# sensor_board_v0_55.net
KiCad netlist of a schematic drawn in EAGLE
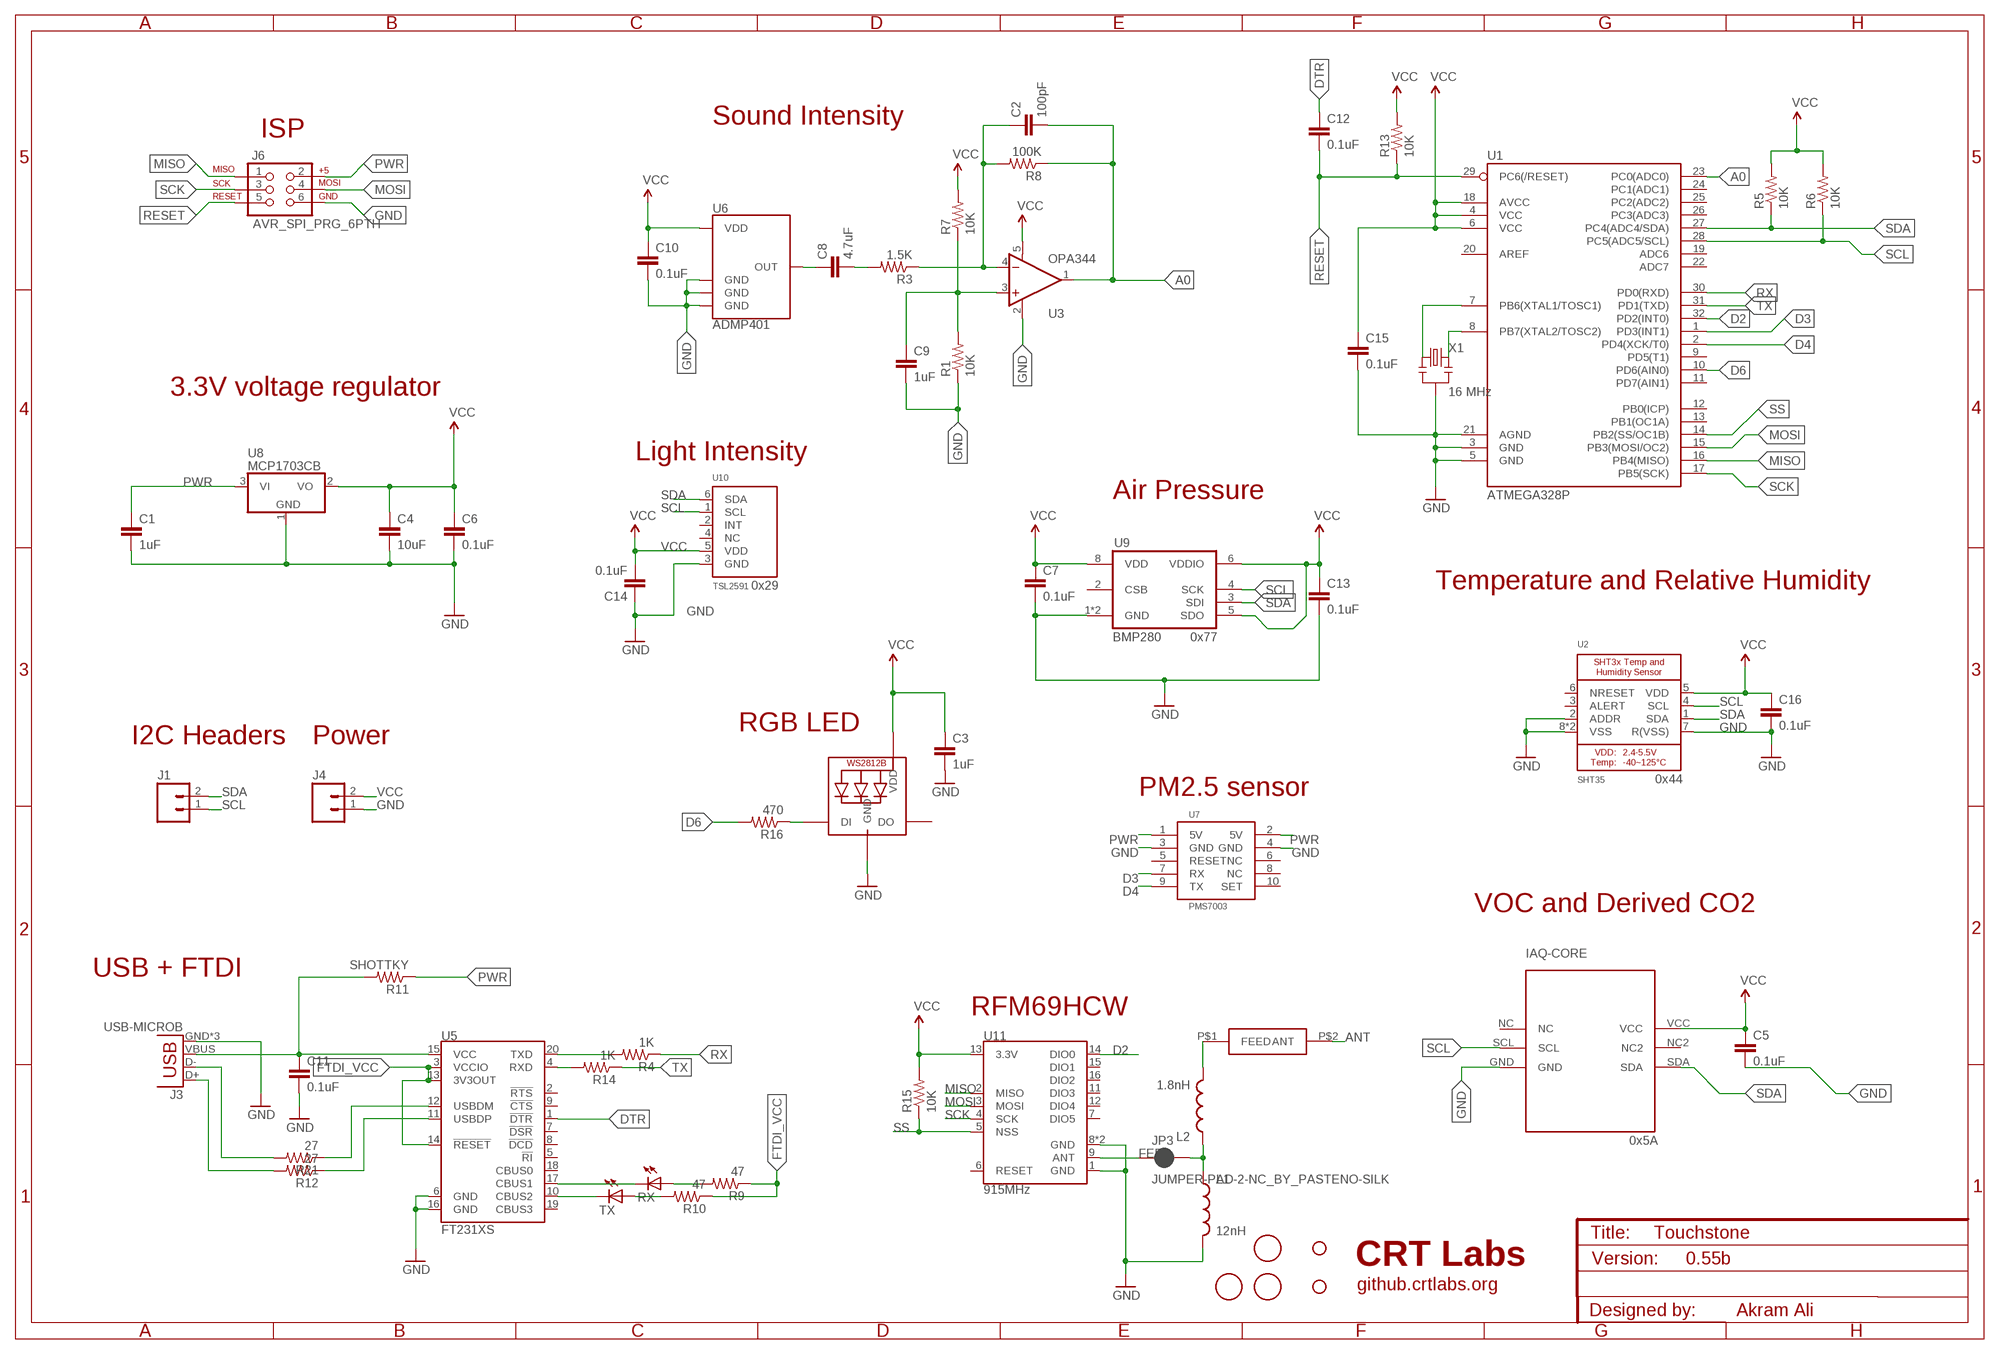
[diagram p0: schematic, sheet 1]

(export (version "E")
  (design (tool "Eeschema 10.0.6"))
  (components
    (comp (ref "C1")
      (value "1uF")
      (footprint "eagle-import:0805")
      (fields (field (name "MPN") "CC0805ZRY5V8BB105"))
      (libsource (lib "eagle-import") (part "CAP0805"))
    )
    (comp (ref "C2")
      (value "100pF")
      (footprint "eagle-import:0805")
      (fields (field (name "MPN") "CC0805JRNPOABN101"))
      (libsource (lib "eagle-import") (part "CAP0805"))
    )
    (comp (ref "C3")
      (value "1uF")
      (footprint "eagle-import:0805")
      (fields (field (name "MPN") "CC0805ZRY5V8BB105"))
      (libsource (lib "eagle-import") (part "CAP0805"))
    )
    (comp (ref "C4")
      (value "10uF")
      (footprint "eagle-import:0805")
      (fields (field (name "MPN") "CC0805KKX5R6BB106"))
      (libsource (lib "eagle-import") (part "CAP0805"))
    )
    (comp (ref "C5")
      (value "0.1uF")
      (footprint "eagle-import:0805")
      (fields (field (name "MPN") "CC0805KRX7R9BB104"))
      (libsource (lib "eagle-import") (part "SparkFun-Passives_CAP0805"))
    )
    (comp (ref "C6")
      (value "0.1uF")
      (footprint "eagle-import:0805")
      (fields (field (name "MPN") "CC0805KRX7R9BB104"))
      (libsource (lib "eagle-import") (part "CAP0805"))
    )
    (comp (ref "C7")
      (value "0.1uF")
      (footprint "eagle-import:0805")
      (fields (field (name "MPN") "CC0805KRX7R9BB104"))
      (libsource (lib "eagle-import") (part "SparkFun-Passives_CAP0805"))
    )
    (comp (ref "C8")
      (value "4.7uF")
      (footprint "eagle-import:0805")
      (fields (field (name "MPN") "CC0805KKX7R6BB475"))
      (libsource (lib "eagle-import") (part "CAP0805"))
    )
    (comp (ref "C9")
      (value "1uF")
      (footprint "eagle-import:0805")
      (fields (field (name "MPN") "CC0805ZRY5V8BB105"))
      (libsource (lib "eagle-import") (part "CAP0805"))
    )
    (comp (ref "C10")
      (value "0.1uF")
      (footprint "eagle-import:0805")
      (fields (field (name "MPN") "CC0805KRX7R9BB104"))
      (libsource (lib "eagle-import") (part "CAP0805"))
    )
    (comp (ref "C11")
      (value "0.1uF")
      (footprint "eagle-import:0805")
      (fields (field (name "MPN") "CC0805KRX7R9BB104"))
      (libsource (lib "eagle-import") (part "CAP0805"))
    )
    (comp (ref "C12")
      (value "0.1uF")
      (footprint "eagle-import:0805")
      (fields (field (name "MPN") "CC0805KRX7R9BB104"))
      (libsource (lib "eagle-import") (part "SparkFun-Passives_CAP0805"))
    )
    (comp (ref "C13")
      (value "0.1uF")
      (footprint "eagle-import:0805")
      (fields (field (name "MPN") "CC0805KRX7R9BB104"))
      (libsource (lib "eagle-import") (part "SparkFun-Passives_CAP0805"))
    )
    (comp (ref "C14")
      (value "0.1uF")
      (footprint "eagle-import:0805")
      (fields (field (name "MPN") "CC0805KRX7R9BB104"))
      (libsource (lib "eagle-import") (part "SparkFun-Passives_CAP0805"))
    )
    (comp (ref "C15")
      (value "0.1uF")
      (footprint "eagle-import:0805")
      (fields (field (name "MPN") "CC0805KRX7R9BB104"))
      (libsource (lib "eagle-import") (part "SparkFun-Passives_CAP0805"))
    )
    (comp (ref "C16")
      (value "0.1uF")
      (footprint "eagle-import:0805")
      (fields (field (name "MPN") "CC0805KRX7R9BB104"))
      (libsource (lib "eagle-import") (part "SparkFun-Passives_CAP0805"))
    )
    (comp (ref "H1")
      (value "STAND-OFF")
      (footprint "eagle-import:STAND-OFF")
      (libsource (lib "eagle-import") (part "STAND-OFF"))
    )
    (comp (ref "H2")
      (value "STAND-OFF")
      (footprint "eagle-import:STAND-OFF")
      (libsource (lib "eagle-import") (part "STAND-OFF"))
    )
    (comp (ref "IAQ-CORE")
      (value "IAQ-CORE")
      (footprint "eagle-import:IAQ-CORE")
      (fields (field (name "MPN") "IAQ-CORE C"))
      (libsource (lib "eagle-import") (part "IAQ-CORE"))
    )
    (comp (ref "J1")
      (value "M02PTH")
      (footprint "eagle-import:1X02")
      (libsource (lib "eagle-import") (part "M02PTH"))
    )
    (comp (ref "J3")
      (value "USB-MICROB")
      (footprint "eagle-import:USB-MICROB")
      (fields (field (name "MPN") "47346-0001"))
      (libsource (lib "eagle-import") (part "USB-MICROB"))
    )
    (comp (ref "J4")
      (value "M02PTH")
      (footprint "eagle-import:1X02")
      (libsource (lib "eagle-import") (part "M02PTH"))
    )
    (comp (ref "J6")
      (value "AVR_SPI_PRG_6PTH")
      (footprint "eagle-import:2X3")
      (libsource (lib "eagle-import") (part "AVR_SPI_PRG_6PTH"))
    )
    (comp (ref "JP3")
      (value "JUMPER-PAD-2-NC_BY_PASTENO-SILK")
      (footprint "eagle-import:PAD-JUMPER-2-NC_BY_PASTE_NO_SILK")
      (libsource (lib "eagle-import") (part "JUMPER-PAD-2-NC_BY_PASTENO-SILK"))
    )
    (comp (ref "L1")
      (value "12nH")
      (footprint "eagle-import:0805")
      (libsource (lib "eagle-import") (part "INDUCTOR0805-IND"))
    )
    (comp (ref "L2")
      (value "1.8nH")
      (footprint "eagle-import:0805")
      (libsource (lib "eagle-import") (part "INDUCTOR0805-IND"))
    )
    (comp (ref "LED1")
      (value "WS2812B3535")
      (footprint "eagle-import:LED3535")
      (fields (field (name "MPN") "SK6812 mini"))
      (libsource (lib "eagle-import") (part "WS2812B3535"))
    )
    (comp (ref "R1")
      (value "10K")
      (footprint "eagle-import:0805")
      (fields (field (name "MPN") "RC0805FR-0710KL"))
      (libsource (lib "eagle-import") (part "RESISTOR0805-RES"))
    )
    (comp (ref "R3")
      (value "1.5K")
      (footprint "eagle-import:0805")
      (fields (field (name "MPN") "RC0805FR-071K5L "))
      (libsource (lib "eagle-import") (part "RESISTOR0805-RES"))
    )
    (comp (ref "R4")
      (value "1K")
      (footprint "eagle-import:0805")
      (fields (field (name "MPN") "RC0805FR-071KL"))
      (libsource (lib "eagle-import") (part "RESISTOR0805-RES"))
    )
    (comp (ref "R5")
      (value "10K")
      (footprint "eagle-import:0805")
      (fields (field (name "MPN") "RC0805FR-0710KL"))
      (libsource (lib "eagle-import") (part "SparkFun-Resistors_RESISTOR0805-RES"))
    )
    (comp (ref "R6")
      (value "10K")
      (footprint "eagle-import:0805")
      (fields (field (name "MPN") "RC0805FR-0710KL"))
      (libsource (lib "eagle-import") (part "SparkFun-Resistors_RESISTOR0805-RES"))
    )
    (comp (ref "R7")
      (value "10K")
      (footprint "eagle-import:0805")
      (fields (field (name "MPN") "RC0805FR-0710KL"))
      (libsource (lib "eagle-import") (part "RESISTOR0805-RES"))
    )
    (comp (ref "R8")
      (value "100K")
      (footprint "eagle-import:0805")
      (fields (field (name "MPN") "RC0805FR-07100KL "))
      (libsource (lib "eagle-import") (part "RESISTOR0805-RES"))
    )
    (comp (ref "R9")
      (value "47")
      (footprint "eagle-import:0805")
      (fields (field (name "MPN") "RC0805FR-0747RL "))
      (libsource (lib "eagle-import") (part "RESISTOR0805-RES"))
    )
    (comp (ref "R10")
      (value "47")
      (footprint "eagle-import:0805")
      (fields (field (name "MPN") "RC0805FR-0747RL "))
      (libsource (lib "eagle-import") (part "RESISTOR0805-RES"))
    )
    (comp (ref "R11")
      (value "SHOTTKY")
      (footprint "eagle-import:0805")
      (fields (field (name "MPN") "SD0805S040S0R5"))
      (libsource (lib "eagle-import") (part "RESISTOR0805-RES"))
    )
    (comp (ref "R12")
      (value "27")
      (footprint "eagle-import:0805")
      (fields (field (name "MPN") "RC0805FR-0727RL "))
      (libsource (lib "eagle-import") (part "RESISTOR0805-RES"))
    )
    (comp (ref "R13")
      (value "10K")
      (footprint "eagle-import:0805")
      (fields (field (name "MPN") "RC0805FR-0710KL"))
      (libsource (lib "eagle-import") (part "RESISTOR0805-RES"))
    )
    (comp (ref "R14")
      (value "1K")
      (footprint "eagle-import:0805")
      (fields (field (name "MPN") "RC0805FR-071KL"))
      (libsource (lib "eagle-import") (part "RESISTOR0805-RES"))
    )
    (comp (ref "R15")
      (value "10K")
      (footprint "eagle-import:0805")
      (fields (field (name "MPN") "RC0805FR-0710KL"))
      (libsource (lib "eagle-import") (part "RESISTOR0805-RES"))
    )
    (comp (ref "R16")
      (value "470")
      (footprint "eagle-import:R0603")
      (fields (field (name "MPN") "RC0805FR-07470RL "))
      (libsource (lib "eagle-import") (part "R-US_R0603"))
    )
    (comp (ref "R21")
      (value "27")
      (footprint "eagle-import:0805")
      (fields (field (name "MPN") "RC0805FR-0727RL "))
      (libsource (lib "eagle-import") (part "RESISTOR0805-RES"))
    )
    (comp (ref "RX")
      (value "LEDCHIPLED_0805")
      (footprint "eagle-import:CHIPLED_0805")
      (fields (field (name "MPN") "LG R971-KN-1"))
      (libsource (lib "eagle-import") (part "LEDCHIPLED_0805"))
    )
    (comp (ref "TX")
      (value "LEDCHIPLED_0805")
      (footprint "eagle-import:CHIPLED_0805")
      (fields (field (name "MPN") "LG R971-KN-1"))
      (libsource (lib "eagle-import") (part "LEDCHIPLED_0805"))
    )
    (comp (ref "U$1")
      (value "FIDUCIAL")
      (footprint "eagle-import:FIDUCIAL_1MM")
      (libsource (lib "eagle-import") (part "FIDUCIAL"))
    )
    (comp (ref "U$2")
      (value "FIDUCIAL")
      (footprint "eagle-import:FIDUCIAL_1MM")
      (libsource (lib "eagle-import") (part "FIDUCIAL"))
    )
    (comp (ref "U$3")
      (value "FIDUCIAL")
      (footprint "eagle-import:FIDUCIAL_1MM")
      (libsource (lib "eagle-import") (part "FIDUCIAL"))
    )
    (comp (ref "U$4")
      (value "0868AT43A0020E")
      (footprint "eagle-import:SMD_CHIP")
      (libsource (lib "eagle-import") (part "0868AT43A0020E"))
    )
    (comp (ref "U1")
      (value "ATMEGA328P")
      (footprint "eagle-import:TQFP32-08")
      (fields (field (name "MPN") "ATMEGA328PB-AU"))
      (libsource (lib "eagle-import") (part "ATMEGA328P_TQFP"))
    )
    (comp (ref "U2")
      (value "SHT35")
      (footprint "eagle-import:SHT3X")
      (fields (field (name "MPN") "SHT35-DIS-B"))
      (libsource (lib "eagle-import") (part "SHT3X"))
    )
    (comp (ref "U3")
      (value "OPA344")
      (footprint "eagle-import:SOT23-5")
      (fields (field (name "MPN") "OPA344NA/3K"))
      (libsource (lib "eagle-import") (part "OPA344"))
    )
    (comp (ref "U5")
      (value "FT231XS")
      (footprint "eagle-import:SSOP20_L")
      (fields (field (name "MPN") "FT231XQ-R"))
      (libsource (lib "eagle-import") (part "FT231XS"))
    )
    (comp (ref "U6")
      (value "ADMP401")
      (footprint "eagle-import:ADMP401")
      (fields (field (name "MPN") "INMP401ACEZ-R7"))
      (libsource (lib "eagle-import") (part "ADMP401"))
    )
    (comp (ref "U7")
      (value "PMS7003")
      (footprint "eagle-import:RECEPTACLE_1.27MM")
      (libsource (lib "eagle-import") (part "PMS7003"))
    )
    (comp (ref "U8")
      (value "MCP1703CB")
      (footprint "eagle-import:SOT23")
      (fields (field (name "MPN") "MCP1703T-2502E/CB"))
      (libsource (lib "eagle-import") (part "MCP1703CB"))
    )
    (comp (ref "U9")
      (value "BMP280")
      (footprint "eagle-import:BMP280")
      (libsource (lib "eagle-import") (part "BMP280"))
    )
    (comp (ref "U10")
      (value "TSL2591")
      (footprint "eagle-import:DFN6_TAOS")
      (fields (field (name "MPN") "TSL25911FN "))
      (libsource (lib "eagle-import") (part "LIGHT_TSL2591"))
    )
    (comp (ref "U11")
      (value "915MHz")
      (footprint "eagle-import:RFM69HCW-XXXS2")
      (libsource (lib "eagle-import") (part "RFM69HCW-915"))
    )
    (comp (ref "X1")
      (value "16 MHz")
      (footprint "eagle-import:RESONATOR-SMD")
      (libsource (lib "eagle-import") (part "RESONATORSMD"))
    )
  )
  (nets
    (net (code "1") (name "/ANT") (class "Default")
      (node (ref "U$4") (pin "P$2") (pinfunction "ANT_P$2") (pintype "bidirectional"))
    )
    (net (code "2") (name "/FEED") (class "Default")
      (node (ref "JP3") (pin "2") (pinfunction "2_2") (pintype "passive"))
      (node (ref "L1") (pin "1") (pinfunction "1_1") (pintype "passive"))
      (node (ref "L2") (pin "1") (pinfunction "1_1") (pintype "passive"))
    )
    (net (code "3") (name "A0") (class "Default")
      (node (ref "C2") (pin "2") (pinfunction "2_2") (pintype "passive"))
      (node (ref "R8") (pin "1") (pinfunction "1_1") (pintype "passive"))
      (node (ref "U1") (pin "23") (pinfunction "PC0(ADC0)_23") (pintype "bidirectional"))
      (node (ref "U3") (pin "1") (pinfunction "OUT_1") (pintype "output"))
    )
    (net (code "4") (name "D2") (class "Default")
      (node (ref "U1") (pin "32") (pinfunction "PD2(INT0)_32") (pintype "bidirectional"))
      (node (ref "U11") (pin "14") (pinfunction "DIO0_14") (pintype "bidirectional"))
    )
    (net (code "5") (name "D3") (class "Default")
      (node (ref "U1") (pin "1") (pinfunction "PD3(INT1)_1") (pintype "bidirectional"))
      (node (ref "U7") (pin "7") (pinfunction "RX_7") (pintype "bidirectional"))
    )
    (net (code "6") (name "D4") (class "Default")
      (node (ref "U1") (pin "2") (pinfunction "PD4(XCK/T0)_2") (pintype "bidirectional"))
      (node (ref "U7") (pin "9") (pinfunction "TX_9") (pintype "bidirectional"))
    )
    (net (code "7") (name "D6") (class "Default")
      (node (ref "R16") (pin "2") (pinfunction "2_2") (pintype "passive"))
      (node (ref "U1") (pin "10") (pinfunction "PD6(AIN0)_10") (pintype "bidirectional"))
    )
    (net (code "8") (name "DTR") (class "Default")
      (node (ref "C12") (pin "1") (pinfunction "1_1") (pintype "passive"))
      (node (ref "U5") (pin "1") (pinfunction "~{DTR}_1") (pintype "bidirectional"))
    )
    (net (code "9") (name "FTDI_VCC") (class "Default")
      (node (ref "R10") (pin "1") (pinfunction "1_1") (pintype "passive"))
      (node (ref "R9") (pin "1") (pinfunction "1_1") (pintype "passive"))
      (node (ref "U5") (pin "13") (pinfunction "3V3OUT_13") (pintype "bidirectional"))
      (node (ref "U5") (pin "14") (pinfunction "~{RESET}_14") (pintype "bidirectional"))
      (node (ref "U5") (pin "3") (pinfunction "VCCIO_3") (pintype "bidirectional"))
    )
    (net (code "10") (name "GND") (class "Default")
      (node (ref "C1") (pin "2") (pinfunction "2_2") (pintype "passive"))
      (node (ref "C10") (pin "2") (pinfunction "2_2") (pintype "passive"))
      (node (ref "C11") (pin "2") (pinfunction "2_2") (pintype "passive"))
      (node (ref "C13") (pin "2") (pinfunction "2_2") (pintype "passive"))
      (node (ref "C14") (pin "1") (pinfunction "1_1") (pintype "passive"))
      (node (ref "C15") (pin "2") (pinfunction "2_2") (pintype "passive"))
      (node (ref "C16") (pin "2") (pinfunction "2_2") (pintype "passive"))
      (node (ref "C3") (pin "2") (pinfunction "2_2") (pintype "passive"))
      (node (ref "C4") (pin "2") (pinfunction "2_2") (pintype "passive"))
      (node (ref "C5") (pin "2") (pinfunction "2_2") (pintype "passive"))
      (node (ref "C6") (pin "2") (pinfunction "2_2") (pintype "passive"))
      (node (ref "C7") (pin "2") (pinfunction "2_2") (pintype "passive"))
      (node (ref "C9") (pin "2") (pinfunction "2_2") (pintype "passive"))
      (node (ref "IAQ-CORE") (pin "GND") (pinfunction "GND_GND") (pintype "bidirectional"))
      (node (ref "J3") (pin "GND") (pinfunction "GND_GND") (pintype "bidirectional"))
      (node (ref "J3") (pin "MT1") (pinfunction "GND_MT1") (pintype "bidirectional"))
      (node (ref "J3") (pin "MT2") (pinfunction "GND_MT2") (pintype "bidirectional"))
      (node (ref "J4") (pin "1") (pinfunction "1_1") (pintype "passive"))
      (node (ref "J6") (pin "6") (pinfunction "6_6") (pintype "passive"))
      (node (ref "L1") (pin "2") (pinfunction "2_2") (pintype "passive"))
      (node (ref "LED1") (pin "4") (pinfunction "GND_4") (pintype "power_in"))
      (node (ref "R1") (pin "1") (pinfunction "1_1") (pintype "passive"))
      (node (ref "U1") (pin "21") (pinfunction "AGND_21") (pintype "bidirectional"))
      (node (ref "U1") (pin "3") (pinfunction "GND_3") (pintype "bidirectional"))
      (node (ref "U1") (pin "5") (pinfunction "GND_5") (pintype "bidirectional"))
      (node (ref "U10") (pin "3") (pinfunction "GND_3") (pintype "power_in"))
      (node (ref "U11") (pin "1") (pinfunction "GND_1") (pintype "power_in"))
      (node (ref "U11") (pin "10") (pinfunction "GND_10") (pintype "power_in"))
      (node (ref "U11") (pin "8") (pinfunction "GND_8") (pintype "power_in"))
      (node (ref "U2") (pin "2") (pinfunction "ADDR_2") (pintype "bidirectional"))
      (node (ref "U2") (pin "7") (pinfunction "R(VSS)_7") (pintype "bidirectional"))
      (node (ref "U2") (pin "8") (pinfunction "VSS_8") (pintype "power_in"))
      (node (ref "U2") (pin "THERMAL") (pinfunction "VSS_THERMAL") (pintype "power_in"))
      (node (ref "U3") (pin "2") (pinfunction "V-_2") (pintype "power_in"))
      (node (ref "U5") (pin "16") (pinfunction "GND_16") (pintype "bidirectional"))
      (node (ref "U5") (pin "6") (pinfunction "GND_6") (pintype "bidirectional"))
      (node (ref "U6") (pin "2") (pinfunction "GND_2") (pintype "bidirectional"))
      (node (ref "U6") (pin "4") (pinfunction "GND_4") (pintype "bidirectional"))
      (node (ref "U6") (pin "6") (pinfunction "GND_6") (pintype "bidirectional"))
      (node (ref "U7") (pin "3") (pinfunction "GND_3") (pintype "bidirectional"))
      (node (ref "U7") (pin "4") (pinfunction "GND_4") (pintype "bidirectional"))
      (node (ref "U8") (pin "1") (pinfunction "GND_1") (pintype "passive"))
      (node (ref "U9") (pin "1") (pinfunction "GND_1") (pintype "power_in"))
      (node (ref "U9") (pin "7") (pinfunction "GND_7") (pintype "power_in"))
      (node (ref "X1") (pin "2") (pinfunction "2_2") (pintype "passive"))
    )
    (net (code "11") (name "MISO") (class "Default")
      (node (ref "J6") (pin "1") (pinfunction "1_1") (pintype "passive"))
      (node (ref "U1") (pin "16") (pinfunction "PB4(MISO)_16") (pintype "bidirectional"))
      (node (ref "U11") (pin "2") (pinfunction "MISO_2") (pintype "bidirectional"))
    )
    (net (code "12") (name "MOSI") (class "Default")
      (node (ref "J6") (pin "4") (pinfunction "4_4") (pintype "passive"))
      (node (ref "U1") (pin "15") (pinfunction "PB3(MOSI/OC2)_15") (pintype "bidirectional"))
      (node (ref "U11") (pin "3") (pinfunction "MOSI_3") (pintype "input"))
    )
    (net (code "13") (name "Net-(C8-Pad2)") (class "Default")
      (node (ref "C8") (pin "2") (pinfunction "2_2") (pintype "passive"))
      (node (ref "R3") (pin "2") (pinfunction "2_2") (pintype "passive"))
    )
    (net (code "14") (name "Net-(J3-PadD+)") (class "Default")
      (node (ref "J3") (pin "D+") (pinfunction "D+_D+") (pintype "bidirectional"))
      (node (ref "R12") (pin "2") (pinfunction "2_2") (pintype "passive"))
    )
    (net (code "15") (name "Net-(J3-PadD-)") (class "Default")
      (node (ref "J3") (pin "D-") (pinfunction "D-_D-") (pintype "bidirectional"))
      (node (ref "R21") (pin "2") (pinfunction "2_2") (pintype "passive"))
    )
    (net (code "16") (name "Net-(LED1-DI)") (class "Default")
      (node (ref "LED1") (pin "1") (pinfunction "DI_1") (pintype "input"))
      (node (ref "R16") (pin "1") (pinfunction "1_1") (pintype "passive"))
    )
    (net (code "17") (name "Net-(R9-Pad2)") (class "Default")
      (node (ref "R9") (pin "2") (pinfunction "2_2") (pintype "passive"))
      (node (ref "RX") (pin "A") (pinfunction "A_A") (pintype "passive"))
    )
    (net (code "18") (name "Net-(R10-Pad2)") (class "Default")
      (node (ref "R10") (pin "2") (pinfunction "2_2") (pintype "passive"))
      (node (ref "TX") (pin "A") (pinfunction "A_A") (pintype "passive"))
    )
    (net (code "19") (name "Net-(U$4-FEED)") (class "Default")
      (node (ref "L2") (pin "2") (pinfunction "2_2") (pintype "passive"))
      (node (ref "U$4") (pin "P$1") (pinfunction "FEED_P$1") (pintype "bidirectional"))
    )
    (net (code "20") (name "Net-(U1-PB6(XTAL1{slash}TOSC1))") (class "Default")
      (node (ref "U1") (pin "7") (pinfunction "PB6(XTAL1/TOSC1)_7") (pintype "bidirectional"))
      (node (ref "X1") (pin "1") (pinfunction "1_1") (pintype "passive"))
    )
    (net (code "21") (name "Net-(U1-PB7(XTAL2{slash}TOSC2))") (class "Default")
      (node (ref "U1") (pin "8") (pinfunction "PB7(XTAL2/TOSC2)_8") (pintype "bidirectional"))
      (node (ref "X1") (pin "3") (pinfunction "3_3") (pintype "passive"))
    )
    (net (code "22") (name "Net-(U3-+IN)") (class "Default")
      (node (ref "C9") (pin "1") (pinfunction "1_1") (pintype "passive"))
      (node (ref "R1") (pin "2") (pinfunction "2_2") (pintype "passive"))
      (node (ref "R7") (pin "1") (pinfunction "1_1") (pintype "passive"))
      (node (ref "U3") (pin "3") (pinfunction "+IN_3") (pintype "input"))
    )
    (net (code "23") (name "Net-(U3--IN)") (class "Default")
      (node (ref "C2") (pin "1") (pinfunction "1_1") (pintype "passive"))
      (node (ref "R3") (pin "1") (pinfunction "1_1") (pintype "passive"))
      (node (ref "R8") (pin "2") (pinfunction "2_2") (pintype "passive"))
      (node (ref "U3") (pin "4") (pinfunction "-IN_4") (pintype "input"))
    )
    (net (code "24") (name "Net-(U5-CBUS1)") (class "Default")
      (node (ref "RX") (pin "C") (pinfunction "C_C") (pintype "passive"))
      (node (ref "U5") (pin "17") (pinfunction "CBUS1_17") (pintype "bidirectional"))
    )
    (net (code "25") (name "Net-(U5-CBUS2)") (class "Default")
      (node (ref "TX") (pin "C") (pinfunction "C_C") (pintype "passive"))
      (node (ref "U5") (pin "10") (pinfunction "CBUS2_10") (pintype "bidirectional"))
    )
    (net (code "26") (name "Net-(U5-RXD)") (class "Default")
      (node (ref "R14") (pin "2") (pinfunction "2_2") (pintype "passive"))
      (node (ref "U5") (pin "4") (pinfunction "RXD_4") (pintype "bidirectional"))
    )
    (net (code "27") (name "Net-(U5-TXD)") (class "Default")
      (node (ref "R4") (pin "2") (pinfunction "2_2") (pintype "passive"))
      (node (ref "U5") (pin "20") (pinfunction "TXD_20") (pintype "bidirectional"))
    )
    (net (code "28") (name "Net-(U5-USBDM)") (class "Default")
      (node (ref "R21") (pin "1") (pinfunction "1_1") (pintype "passive"))
      (node (ref "U5") (pin "12") (pinfunction "USBDM_12") (pintype "bidirectional"))
    )
    (net (code "29") (name "Net-(U5-USBDP)") (class "Default")
      (node (ref "R12") (pin "1") (pinfunction "1_1") (pintype "passive"))
      (node (ref "U5") (pin "11") (pinfunction "USBDP_11") (pintype "bidirectional"))
    )
    (net (code "30") (name "Net-(U5-VCC)") (class "Default")
      (node (ref "C11") (pin "1") (pinfunction "1_1") (pintype "passive"))
      (node (ref "J3") (pin "VBUS") (pinfunction "VBUS_VBUS") (pintype "bidirectional"))
      (node (ref "R11") (pin "2") (pinfunction "2_2") (pintype "passive"))
      (node (ref "U5") (pin "15") (pinfunction "VCC_15") (pintype "bidirectional"))
    )
    (net (code "31") (name "Net-(U6-OUT)") (class "Default")
      (node (ref "C8") (pin "1") (pinfunction "1_1") (pintype "passive"))
      (node (ref "U6") (pin "1") (pinfunction "OUT_1") (pintype "bidirectional"))
    )
    (net (code "32") (name "Net-(U11-ANT)") (class "Default")
      (node (ref "JP3") (pin "1") (pinfunction "1_1") (pintype "passive"))
      (node (ref "U11") (pin "9") (pinfunction "ANT_9") (pintype "passive"))
    )
    (net (code "33") (name "PWR") (class "Default")
      (node (ref "C1") (pin "1") (pinfunction "1_1") (pintype "passive"))
      (node (ref "J6") (pin "2") (pinfunction "2_2") (pintype "passive"))
      (node (ref "R11") (pin "1") (pinfunction "1_1") (pintype "passive"))
      (node (ref "U7") (pin "1") (pinfunction "5V_1") (pintype "bidirectional"))
      (node (ref "U7") (pin "2") (pinfunction "5V_2") (pintype "bidirectional"))
      (node (ref "U8") (pin "3") (pinfunction "VI_3") (pintype "input"))
    )
    (net (code "34") (name "RESET") (class "Default")
      (node (ref "C12") (pin "2") (pinfunction "2_2") (pintype "passive"))
      (node (ref "J6") (pin "5") (pinfunction "5_5") (pintype "passive"))
      (node (ref "R13") (pin "1") (pinfunction "1_1") (pintype "passive"))
      (node (ref "U1") (pin "29") (pinfunction "PC6(/RESET)_29") (pintype "bidirectional"))
    )
    (net (code "35") (name "RX") (class "Default")
      (node (ref "R4") (pin "1") (pinfunction "1_1") (pintype "passive"))
      (node (ref "U1") (pin "30") (pinfunction "PD0(RXD)_30") (pintype "bidirectional"))
    )
    (net (code "36") (name "SCK") (class "Default")
      (node (ref "J6") (pin "3") (pinfunction "3_3") (pintype "passive"))
      (node (ref "U1") (pin "17") (pinfunction "PB5(SCK)_17") (pintype "bidirectional"))
      (node (ref "U11") (pin "4") (pinfunction "SCK_4") (pintype "input"))
    )
    (net (code "37") (name "SCL") (class "Default")
      (node (ref "IAQ-CORE") (pin "SCL") (pinfunction "SCL_SCL") (pintype "bidirectional"))
      (node (ref "J1") (pin "1") (pinfunction "1_1") (pintype "passive"))
      (node (ref "R6") (pin "1") (pinfunction "1_1") (pintype "passive"))
      (node (ref "U1") (pin "28") (pinfunction "PC5(ADC5/SCL)_28") (pintype "bidirectional"))
      (node (ref "U10") (pin "1") (pinfunction "SCL_1") (pintype "bidirectional"))
      (node (ref "U2") (pin "4") (pinfunction "SCL_4") (pintype "bidirectional"))
      (node (ref "U9") (pin "4") (pinfunction "SCK_4") (pintype "bidirectional"))
    )
    (net (code "38") (name "SDA") (class "Default")
      (node (ref "IAQ-CORE") (pin "SDA") (pinfunction "SDA_SDA") (pintype "bidirectional"))
      (node (ref "J1") (pin "2") (pinfunction "2_2") (pintype "passive"))
      (node (ref "R5") (pin "1") (pinfunction "1_1") (pintype "passive"))
      (node (ref "U1") (pin "27") (pinfunction "PC4(ADC4/SDA)_27") (pintype "bidirectional"))
      (node (ref "U10") (pin "6") (pinfunction "SDA_6") (pintype "bidirectional"))
      (node (ref "U2") (pin "1") (pinfunction "SDA_1") (pintype "bidirectional"))
      (node (ref "U9") (pin "3") (pinfunction "SDI_3") (pintype "bidirectional"))
    )
    (net (code "39") (name "SS") (class "Default")
      (node (ref "R15") (pin "1") (pinfunction "1_1") (pintype "passive"))
      (node (ref "U1") (pin "14") (pinfunction "PB2(SS/OC1B)_14") (pintype "bidirectional"))
      (node (ref "U11") (pin "5") (pinfunction "NSS_5") (pintype "input"))
    )
    (net (code "40") (name "TX") (class "Default")
      (node (ref "R14") (pin "1") (pinfunction "1_1") (pintype "passive"))
      (node (ref "U1") (pin "31") (pinfunction "PD1(TXD)_31") (pintype "bidirectional"))
    )
    (net (code "41") (name "VCC") (class "Default")
      (node (ref "C10") (pin "1") (pinfunction "1_1") (pintype "passive"))
      (node (ref "C13") (pin "1") (pinfunction "1_1") (pintype "passive"))
      (node (ref "C14") (pin "2") (pinfunction "2_2") (pintype "passive"))
      (node (ref "C15") (pin "1") (pinfunction "1_1") (pintype "passive"))
      (node (ref "C16") (pin "1") (pinfunction "1_1") (pintype "passive"))
      (node (ref "C3") (pin "1") (pinfunction "1_1") (pintype "passive"))
      (node (ref "C4") (pin "1") (pinfunction "1_1") (pintype "passive"))
      (node (ref "C5") (pin "1") (pinfunction "1_1") (pintype "passive"))
      (node (ref "C6") (pin "1") (pinfunction "1_1") (pintype "passive"))
      (node (ref "C7") (pin "1") (pinfunction "1_1") (pintype "passive"))
      (node (ref "IAQ-CORE") (pin "VCC") (pinfunction "VCC_VCC") (pintype "bidirectional"))
      (node (ref "J4") (pin "2") (pinfunction "2_2") (pintype "passive"))
      (node (ref "LED1") (pin "2") (pinfunction "VDD_2") (pintype "power_in"))
      (node (ref "R13") (pin "2") (pinfunction "2_2") (pintype "passive"))
      (node (ref "R15") (pin "2") (pinfunction "2_2") (pintype "passive"))
      (node (ref "R5") (pin "2") (pinfunction "2_2") (pintype "passive"))
      (node (ref "R6") (pin "2") (pinfunction "2_2") (pintype "passive"))
      (node (ref "R7") (pin "2") (pinfunction "2_2") (pintype "passive"))
      (node (ref "U1") (pin "18") (pinfunction "AVCC_18") (pintype "bidirectional"))
      (node (ref "U1") (pin "4") (pinfunction "VCC_4") (pintype "bidirectional"))
      (node (ref "U1") (pin "6") (pinfunction "VCC_6") (pintype "bidirectional"))
      (node (ref "U10") (pin "5") (pinfunction "VDD_5") (pintype "power_in"))
      (node (ref "U11") (pin "13") (pinfunction "3.3V_13") (pintype "power_in"))
      (node (ref "U2") (pin "5") (pinfunction "VDD_5") (pintype "power_in"))
      (node (ref "U3") (pin "5") (pinfunction "V+_5") (pintype "power_in"))
      (node (ref "U6") (pin "5") (pinfunction "VDD_5") (pintype "bidirectional"))
      (node (ref "U8") (pin "2") (pinfunction "VO_2") (pintype "passive"))
      (node (ref "U9") (pin "5") (pinfunction "SDO_5") (pintype "input"))
      (node (ref "U9") (pin "6") (pinfunction "VDDIO_6") (pintype "power_in"))
      (node (ref "U9") (pin "8") (pinfunction "VDD_8") (pintype "power_in"))
    )
    (net (code "42") (name "unconnected-(IAQ-CORE-PadNC)") (class "Default")
      (node (ref "IAQ-CORE") (pin "NC") (pinfunction "NC_NC") (pintype "bidirectional"))
    )
    (net (code "43") (name "unconnected-(IAQ-CORE-PadNC2)") (class "Default")
      (node (ref "IAQ-CORE") (pin "NC2") (pinfunction "NC2_NC2") (pintype "bidirectional"))
    )
    (net (code "44") (name "unconnected-(LED1-DO-Pad3)") (class "Default")
      (node (ref "LED1") (pin "3") (pinfunction "DO_3") (pintype "output"))
    )
    (net (code "45") (name "unconnected-(U1-ADC6-Pad19)") (class "Default")
      (node (ref "U1") (pin "19") (pinfunction "ADC6_19") (pintype "bidirectional"))
    )
    (net (code "46") (name "unconnected-(U1-ADC7-Pad22)") (class "Default")
      (node (ref "U1") (pin "22") (pinfunction "ADC7_22") (pintype "bidirectional"))
    )
    (net (code "47") (name "unconnected-(U1-AREF-Pad20)") (class "Default")
      (node (ref "U1") (pin "20") (pinfunction "AREF_20") (pintype "bidirectional"))
    )
    (net (code "48") (name "unconnected-(U1-PB0(ICP)-Pad12)") (class "Default")
      (node (ref "U1") (pin "12") (pinfunction "PB0(ICP)_12") (pintype "bidirectional"))
    )
    (net (code "49") (name "unconnected-(U1-PB1(OC1A)-Pad13)") (class "Default")
      (node (ref "U1") (pin "13") (pinfunction "PB1(OC1A)_13") (pintype "bidirectional"))
    )
    (net (code "50") (name "unconnected-(U1-PC1(ADC1)-Pad24)") (class "Default")
      (node (ref "U1") (pin "24") (pinfunction "PC1(ADC1)_24") (pintype "bidirectional"))
    )
    (net (code "51") (name "unconnected-(U1-PC2(ADC2)-Pad25)") (class "Default")
      (node (ref "U1") (pin "25") (pinfunction "PC2(ADC2)_25") (pintype "bidirectional"))
    )
    (net (code "52") (name "unconnected-(U1-PC3(ADC3)-Pad26)") (class "Default")
      (node (ref "U1") (pin "26") (pinfunction "PC3(ADC3)_26") (pintype "bidirectional"))
    )
    (net (code "53") (name "unconnected-(U1-PD5(T1)-Pad9)") (class "Default")
      (node (ref "U1") (pin "9") (pinfunction "PD5(T1)_9") (pintype "bidirectional"))
    )
    (net (code "54") (name "unconnected-(U1-PD7(AIN1)-Pad11)") (class "Default")
      (node (ref "U1") (pin "11") (pinfunction "PD7(AIN1)_11") (pintype "bidirectional"))
    )
    (net (code "55") (name "unconnected-(U2-ALERT-Pad3)") (class "Default")
      (node (ref "U2") (pin "3") (pinfunction "ALERT_3") (pintype "bidirectional"))
    )
    (net (code "56") (name "unconnected-(U2-NRESET-Pad6)") (class "Default")
      (node (ref "U2") (pin "6") (pinfunction "NRESET_6") (pintype "bidirectional"))
    )
    (net (code "57") (name "unconnected-(U5-CBUS0-Pad18)") (class "Default")
      (node (ref "U5") (pin "18") (pinfunction "CBUS0_18") (pintype "bidirectional"))
    )
    (net (code "58") (name "unconnected-(U5-CBUS3-Pad19)") (class "Default")
      (node (ref "U5") (pin "19") (pinfunction "CBUS3_19") (pintype "bidirectional"))
    )
    (net (code "59") (name "unconnected-(U5-~{CTS}-Pad9)") (class "Default")
      (node (ref "U5") (pin "9") (pinfunction "~{CTS}_9") (pintype "bidirectional"))
    )
    (net (code "60") (name "unconnected-(U5-~{DCD}-Pad8)") (class "Default")
      (node (ref "U5") (pin "8") (pinfunction "~{DCD}_8") (pintype "bidirectional"))
    )
    (net (code "61") (name "unconnected-(U5-~{DSR}-Pad7)") (class "Default")
      (node (ref "U5") (pin "7") (pinfunction "~{DSR}_7") (pintype "bidirectional"))
    )
    (net (code "62") (name "unconnected-(U5-~{RI}-Pad5)") (class "Default")
      (node (ref "U5") (pin "5") (pinfunction "~{RI}_5") (pintype "bidirectional"))
    )
    (net (code "63") (name "unconnected-(U5-~{RTS}-Pad2)") (class "Default")
      (node (ref "U5") (pin "2") (pinfunction "~{RTS}_2") (pintype "bidirectional"))
    )
    (net (code "64") (name "unconnected-(U7-NC-Pad6)") (class "Default")
      (node (ref "U7") (pin "6") (pinfunction "NC_6") (pintype "bidirectional"))
    )
    (net (code "65") (name "unconnected-(U7-NC-Pad8)") (class "Default")
      (node (ref "U7") (pin "8") (pinfunction "NC_8") (pintype "bidirectional"))
    )
    (net (code "66") (name "unconnected-(U7-RESET-Pad5)") (class "Default")
      (node (ref "U7") (pin "5") (pinfunction "RESET_5") (pintype "bidirectional"))
    )
    (net (code "67") (name "unconnected-(U7-SET-Pad10)") (class "Default")
      (node (ref "U7") (pin "10") (pinfunction "SET_10") (pintype "bidirectional"))
    )
    (net (code "68") (name "unconnected-(U9-CSB-Pad2)") (class "Default")
      (node (ref "U9") (pin "2") (pinfunction "CSB_2") (pintype "input"))
    )
    (net (code "69") (name "unconnected-(U10-INT-Pad2)") (class "Default")
      (node (ref "U10") (pin "2") (pinfunction "INT_2") (pintype "output"))
    )
    (net (code "70") (name "unconnected-(U10-NC-Pad4)") (class "Default")
      (node (ref "U10") (pin "4") (pinfunction "NC_4") (pintype "no_connect"))
    )
    (net (code "71") (name "unconnected-(U11-DIO1-Pad15)") (class "Default")
      (node (ref "U11") (pin "15") (pinfunction "DIO1_15") (pintype "bidirectional"))
    )
    (net (code "72") (name "unconnected-(U11-DIO2-Pad16)") (class "Default")
      (node (ref "U11") (pin "16") (pinfunction "DIO2_16") (pintype "bidirectional"))
    )
    (net (code "73") (name "unconnected-(U11-DIO3-Pad11)") (class "Default")
      (node (ref "U11") (pin "11") (pinfunction "DIO3_11") (pintype "bidirectional"))
    )
    (net (code "74") (name "unconnected-(U11-DIO4-Pad12)") (class "Default")
      (node (ref "U11") (pin "12") (pinfunction "DIO4_12") (pintype "bidirectional"))
    )
    (net (code "75") (name "unconnected-(U11-DIO5-Pad7)") (class "Default")
      (node (ref "U11") (pin "7") (pinfunction "DIO5_7") (pintype "bidirectional"))
    )
    (net (code "76") (name "unconnected-(U11-RESET-Pad6)") (class "Default")
      (node (ref "U11") (pin "6") (pinfunction "RESET_6") (pintype "input"))
    )
  )
)
